# GRF2071_testboard.net
KiCad netlist of a schematic drawn in Altium Designer
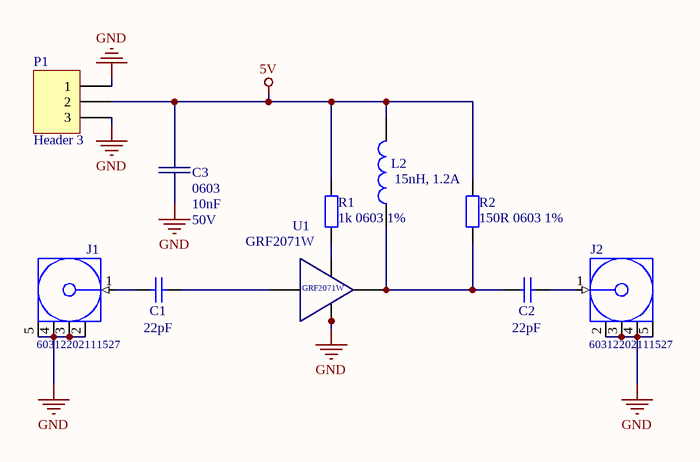
[diagram p0: GRF2071_testboard.SchDoc]

(export (version "E")
  (design (tool "Eeschema 10.0.6"))
  (components
    (comp (ref "C1")
      (value "22pF")
      (footprint "WCAP-CSRF_0402_L1W0.5H0.5")
      (description "WCAP-CSRF Multilayer Ceramic Chip Capacitor, High Frequency, 0402, NP0 Class I, 22pF, 50VDC")
      (fields
        (field (name "MANUFACTURER") "Wurth Elektronik")
        (field (name "MANUFACTURER PART NUMBER") "885392005114")
      )
      (libsource (lib "Altium_WCAP-CSRF (rev22c)") (part "885392005114"))
    )
    (comp (ref "C2")
      (value "22pF")
      (footprint "WCAP-CSRF_0402_L1W0.5H0.5")
      (description "WCAP-CSRF Multilayer Ceramic Chip Capacitor, High Frequency, 0402, NP0 Class I, 22pF, 50VDC")
      (fields
        (field (name "MANUFACTURER") "Wurth Elektronik")
        (field (name "MANUFACTURER PART NUMBER") "885392005114")
      )
      (libsource (lib "Altium_WCAP-CSRF (rev22c)") (part "885392005114"))
    )
    (comp (ref "C3")
      (value "10nF 0603 NP0")
      (footprint "C0603_murata")
      (description "10nF 0603 NP0 muRata")
      (fields
        (field (name "TOLERANCE") "5%")
        (field (name "CASE CODE (IMPERIAL)") "0603")
        (field (name "CAPACITANCE") "10nF")
        (field (name "VOLTAGE") "50V")
      )
      (libsource (lib "ftg_lib") (part "CAP 10nF 0603 NP0"))
    )
    (comp (ref "J1")
      (value "60312202111527")
      (footprint "60312202111527")
      (description "WR-SMA Connector, PCB End Launch Jack, 6.35SQ Flange Round Post for PCB 1.6mm, DC~18GHz, 50Ohm")
      (fields (field (name "MANUFACTURER") "Wurth Elektronik"))
      (libsource (lib "Altium_WR-SMA (rev21c)") (part "60312202111527"))
    )
    (comp (ref "J2")
      (value "60312202111527")
      (footprint "60312202111527")
      (description "WR-SMA Connector, PCB End Launch Jack, 6.35SQ Flange Round Post for PCB 1.6mm, DC~18GHz, 50Ohm")
      (fields (field (name "MANUFACTURER") "Wurth Elektronik"))
      (libsource (lib "Altium_WR-SMA (rev21c)") (part "60312202111527"))
    )
    (comp (ref "L2")
      (value "15nH, 1.2A")
      (footprint "WE-KI HC_0603")
      (description "WE-KI HC SMT High Current Wire Wound Ceramic Inductor, size 0603, 15nH, 1.2A")
      (fields
        (field (name "MANUFACTURER") "Wurth Elektronik")
        (field (name "MANUFACTURER PART NUMBER") "744917115")
      )
      (libsource (lib "Altium_WE-KI HC (rev22a)") (part "744917115"))
    )
    (comp (ref "P1")
      (value "Header 3")
      (footprint "HDR1X3")
      (description "Header, 3-Pin")
      (fields (field (name "PUBLISHER") "Altium Limited"))
      (libsource (lib "Miscellaneous Connectors") (part "Header 3"))
    )
    (comp (ref "R1")
      (value "1k 0603 1%")
      (footprint "R0603")
      (fields (field (name "TOLERANCE") "1%") (field (name "PUBLISHER") "iv"))
      (libsource (lib "ftg_lib") (part "RES 1k 0603"))
    )
    (comp (ref "R2")
      (value "150R 0603 1%")
      (footprint "R0603")
      (fields (field (name "TOLERANCE") "1%") (field (name "PUBLISHER") "iv"))
      (libsource (lib "ftg_lib") (part "RES 150R 0603"))
    )
    (comp (ref "U1")
      (value "GRF2071W")
      (footprint "GRF_DFN8_2x2mm")
      (description "0.7 - 2.7 GHz Ultra-Low Noise Amplifier AEC-Q100")
      (libsource (lib "ftg_lib") (part "GRF2071W"))
    )
  )
  (nets
    (net (code "1") (name "5V") (class "Default")
      (node (ref "C3") (pin "2") (pinfunction "2_2") (pintype "passive"))
      (node (ref "L2") (pin "2") (pinfunction "2_2") (pintype "passive"))
      (node (ref "P1") (pin "2") (pinfunction "2_2") (pintype "passive"))
      (node (ref "R1") (pin "2") (pinfunction "2_2") (pintype "passive"))
      (node (ref "R2") (pin "2") (pinfunction "2_2") (pintype "passive"))
    )
    (net (code "2") (name "GND") (class "Default")
      (node (ref "C3") (pin "1") (pinfunction "1_1") (pintype "passive"))
      (node (ref "J1") (pin "2") (pinfunction "GND_2") (pintype "power_in"))
      (node (ref "J1") (pin "3") (pinfunction "GND_3") (pintype "power_in"))
      (node (ref "J1") (pin "4") (pinfunction "GND_4") (pintype "power_in"))
      (node (ref "J1") (pin "5") (pinfunction "GND_5") (pintype "power_in"))
      (node (ref "J2") (pin "2") (pinfunction "GND_2") (pintype "power_in"))
      (node (ref "J2") (pin "3") (pinfunction "GND_3") (pintype "power_in"))
      (node (ref "J2") (pin "4") (pinfunction "GND_4") (pintype "power_in"))
      (node (ref "J2") (pin "5") (pinfunction "GND_5") (pintype "power_in"))
      (node (ref "P1") (pin "1") (pinfunction "1_1") (pintype "passive"))
      (node (ref "P1") (pin "3") (pinfunction "3_3") (pintype "passive"))
      (node (ref "U1") (pin "3") (pinfunction "6_3") (pintype "passive"))
      (node (ref "U1") (pin "4") (pinfunction "GND_4") (pintype "passive"))
      (node (ref "U1") (pin "5") (pinfunction "GND_5") (pintype "passive"))
      (node (ref "U1") (pin "8") (pinfunction "GND_8") (pintype "passive"))
      (node (ref "U1") (pin "9") (pinfunction "GND_9") (pintype "passive"))
    )
    (net (code "3") (name "Net-(J1-Signal)") (class "Default")
      (node (ref "C1") (pin "1") (pinfunction "1_1") (pintype "passive"))
      (node (ref "J1") (pin "1") (pinfunction "Signal_1") (pintype "input"))
    )
    (net (code "4") (name "Net-(J2-Signal)") (class "Default")
      (node (ref "C2") (pin "2") (pinfunction "2_2") (pintype "passive"))
      (node (ref "J2") (pin "1") (pinfunction "Signal_1") (pintype "input"))
    )
    (net (code "5") (name "Net-(U1-RF_In)") (class "Default")
      (node (ref "C1") (pin "2") (pinfunction "2_2") (pintype "passive"))
      (node (ref "U1") (pin "2") (pinfunction "RF_In_2") (pintype "passive"))
    )
    (net (code "6") (name "Net-(U1-RF_Out)") (class "Default")
      (node (ref "C2") (pin "1") (pinfunction "1_1") (pintype "passive"))
      (node (ref "L2") (pin "1") (pinfunction "1_1") (pintype "passive"))
      (node (ref "R2") (pin "1") (pinfunction "1_1") (pintype "passive"))
      (node (ref "U1") (pin "7") (pinfunction "RF_Out_7") (pintype "passive"))
    )
    (net (code "7") (name "Net-(U1-Venable)") (class "Default")
      (node (ref "R1") (pin "1") (pinfunction "1_1") (pintype "passive"))
      (node (ref "U1") (pin "1") (pinfunction "Venable_1") (pintype "passive"))
    )
  )
)
